# Buttons.net
KiCad netlist of a schematic drawn in Altium Designer
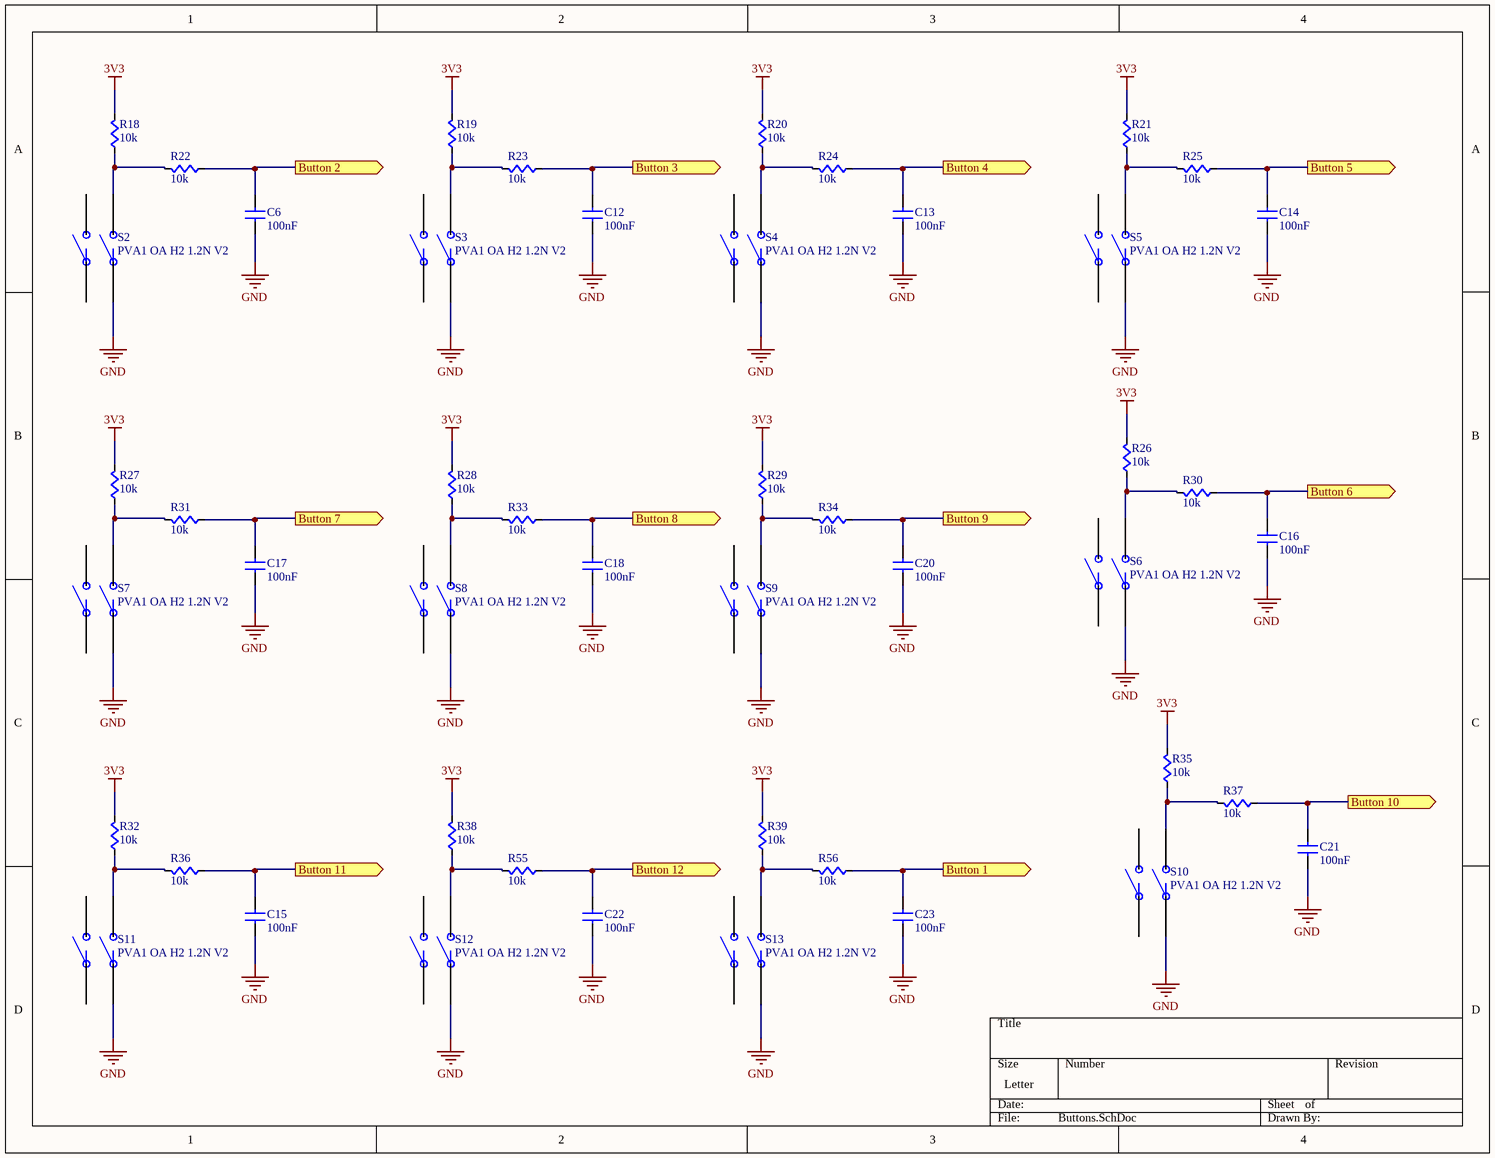
[diagram p0: Buttons.SchDoc]

(export (version "E")
  (design (tool "Eeschema 10.0.6"))
  (components
    (comp (ref "C6")
      (value "100nF")
      (footprint "CAPC0603")
      (fields (field (name "Comment") "Cap"))
      (libsource (lib "SubjuGator8") (part "Cap"))
    )
    (comp (ref "C12")
      (value "100nF")
      (footprint "CAPC0603")
      (fields (field (name "Comment") "Cap"))
      (libsource (lib "SubjuGator8") (part "Cap"))
    )
    (comp (ref "C13")
      (value "100nF")
      (footprint "CAPC0603")
      (fields (field (name "Comment") "Cap"))
      (libsource (lib "SubjuGator8") (part "Cap"))
    )
    (comp (ref "C14")
      (value "100nF")
      (footprint "CAPC0603")
      (fields (field (name "Comment") "Cap"))
      (libsource (lib "SubjuGator8") (part "Cap"))
    )
    (comp (ref "C15")
      (value "100nF")
      (footprint "CAPC0603")
      (fields (field (name "Comment") "Cap"))
      (libsource (lib "SubjuGator8") (part "Cap"))
    )
    (comp (ref "C16")
      (value "100nF")
      (footprint "CAPC0603")
      (fields (field (name "Comment") "Cap"))
      (libsource (lib "SubjuGator8") (part "Cap"))
    )
    (comp (ref "C17")
      (value "100nF")
      (footprint "CAPC0603")
      (fields (field (name "Comment") "Cap"))
      (libsource (lib "SubjuGator8") (part "Cap"))
    )
    (comp (ref "C18")
      (value "100nF")
      (footprint "CAPC0603")
      (fields (field (name "Comment") "Cap"))
      (libsource (lib "SubjuGator8") (part "Cap"))
    )
    (comp (ref "C20")
      (value "100nF")
      (footprint "CAPC0603")
      (fields (field (name "Comment") "Cap"))
      (libsource (lib "SubjuGator8") (part "Cap"))
    )
    (comp (ref "C21")
      (value "100nF")
      (footprint "CAPC0603")
      (fields (field (name "Comment") "Cap"))
      (libsource (lib "SubjuGator8") (part "Cap"))
    )
    (comp (ref "C22")
      (value "100nF")
      (footprint "CAPC0603")
      (fields (field (name "Comment") "Cap"))
      (libsource (lib "SubjuGator8") (part "Cap"))
    )
    (comp (ref "C23")
      (value "100nF")
      (footprint "CAPC0603")
      (fields (field (name "Comment") "Cap"))
      (libsource (lib "SubjuGator8") (part "Cap"))
    )
    (comp (ref "R18")
      (value "10k")
      (footprint "RES0603")
      (fields (field (name "Comment") "Res"))
      (libsource (lib "SubjuGator8") (part "Res"))
    )
    (comp (ref "R19")
      (value "10k")
      (footprint "RES0603")
      (fields (field (name "Comment") "Res"))
      (libsource (lib "SubjuGator8") (part "Res"))
    )
    (comp (ref "R20")
      (value "10k")
      (footprint "RES0603")
      (fields (field (name "Comment") "Res"))
      (libsource (lib "SubjuGator8") (part "Res"))
    )
    (comp (ref "R21")
      (value "10k")
      (footprint "RES0603")
      (fields (field (name "Comment") "Res"))
      (libsource (lib "SubjuGator8") (part "Res"))
    )
    (comp (ref "R22")
      (value "10k")
      (footprint "RES0603")
      (fields (field (name "Comment") "Res"))
      (libsource (lib "SubjuGator8") (part "Res"))
    )
    (comp (ref "R23")
      (value "10k")
      (footprint "RES0603")
      (fields (field (name "Comment") "Res"))
      (libsource (lib "SubjuGator8") (part "Res"))
    )
    (comp (ref "R24")
      (value "10k")
      (footprint "RES0603")
      (fields (field (name "Comment") "Res"))
      (libsource (lib "SubjuGator8") (part "Res"))
    )
    (comp (ref "R25")
      (value "10k")
      (footprint "RES0603")
      (fields (field (name "Comment") "Res"))
      (libsource (lib "SubjuGator8") (part "Res"))
    )
    (comp (ref "R26")
      (value "10k")
      (footprint "RES0603")
      (fields (field (name "Comment") "Res"))
      (libsource (lib "SubjuGator8") (part "Res"))
    )
    (comp (ref "R27")
      (value "10k")
      (footprint "RES0603")
      (fields (field (name "Comment") "Res"))
      (libsource (lib "SubjuGator8") (part "Res"))
    )
    (comp (ref "R28")
      (value "10k")
      (footprint "RES0603")
      (fields (field (name "Comment") "Res"))
      (libsource (lib "SubjuGator8") (part "Res"))
    )
    (comp (ref "R29")
      (value "10k")
      (footprint "RES0603")
      (fields (field (name "Comment") "Res"))
      (libsource (lib "SubjuGator8") (part "Res"))
    )
    (comp (ref "R30")
      (value "10k")
      (footprint "RES0603")
      (fields (field (name "Comment") "Res"))
      (libsource (lib "SubjuGator8") (part "Res"))
    )
    (comp (ref "R31")
      (value "10k")
      (footprint "RES0603")
      (fields (field (name "Comment") "Res"))
      (libsource (lib "SubjuGator8") (part "Res"))
    )
    (comp (ref "R32")
      (value "10k")
      (footprint "RES0603")
      (fields (field (name "Comment") "Res"))
      (libsource (lib "SubjuGator8") (part "Res"))
    )
    (comp (ref "R33")
      (value "10k")
      (footprint "RES0603")
      (fields (field (name "Comment") "Res"))
      (libsource (lib "SubjuGator8") (part "Res"))
    )
    (comp (ref "R34")
      (value "10k")
      (footprint "RES0603")
      (fields (field (name "Comment") "Res"))
      (libsource (lib "SubjuGator8") (part "Res"))
    )
    (comp (ref "R35")
      (value "10k")
      (footprint "RES0603")
      (fields (field (name "Comment") "Res"))
      (libsource (lib "SubjuGator8") (part "Res"))
    )
    (comp (ref "R36")
      (value "10k")
      (footprint "RES0603")
      (fields (field (name "Comment") "Res"))
      (libsource (lib "SubjuGator8") (part "Res"))
    )
    (comp (ref "R37")
      (value "10k")
      (footprint "RES0603")
      (fields (field (name "Comment") "Res"))
      (libsource (lib "SubjuGator8") (part "Res"))
    )
    (comp (ref "R38")
      (value "10k")
      (footprint "RES0603")
      (fields (field (name "Comment") "Res"))
      (libsource (lib "SubjuGator8") (part "Res"))
    )
    (comp (ref "R39")
      (value "10k")
      (footprint "RES0603")
      (fields (field (name "Comment") "Res"))
      (libsource (lib "SubjuGator8") (part "Res"))
    )
    (comp (ref "R55")
      (value "10k")
      (footprint "RES0603")
      (fields (field (name "Comment") "Res"))
      (libsource (lib "SubjuGator8") (part "Res"))
    )
    (comp (ref "R56")
      (value "10k")
      (footprint "RES0603")
      (fields (field (name "Comment") "Res"))
      (libsource (lib "SubjuGator8") (part "Res"))
    )
    (comp (ref "S2")
      (value "PVA1 OA H2 1.2N V2")
      (footprint "PVA1 OA H2 1.2N V2")
      (description "Pushbutton Switch DPST-NO Keyswitch Through Hole")
      (fields (field (name "MANUFACTURER") "C&K"))
      (libsource (lib "SubjuGator8") (part "PVA1 OA H2 1.2N V2"))
    )
    (comp (ref "S3")
      (value "PVA1 OA H2 1.2N V2")
      (footprint "PVA1 OA H2 1.2N V2")
      (description "Pushbutton Switch DPST-NO Keyswitch Through Hole")
      (fields (field (name "MANUFACTURER") "C&K"))
      (libsource (lib "SubjuGator8") (part "PVA1 OA H2 1.2N V2"))
    )
    (comp (ref "S4")
      (value "PVA1 OA H2 1.2N V2")
      (footprint "PVA1 OA H2 1.2N V2")
      (description "Pushbutton Switch DPST-NO Keyswitch Through Hole")
      (fields (field (name "MANUFACTURER") "C&K"))
      (libsource (lib "SubjuGator8") (part "PVA1 OA H2 1.2N V2"))
    )
    (comp (ref "S5")
      (value "PVA1 OA H2 1.2N V2")
      (footprint "PVA1 OA H2 1.2N V2")
      (description "Pushbutton Switch DPST-NO Keyswitch Through Hole")
      (fields (field (name "MANUFACTURER") "C&K"))
      (libsource (lib "SubjuGator8") (part "PVA1 OA H2 1.2N V2"))
    )
    (comp (ref "S6")
      (value "PVA1 OA H2 1.2N V2")
      (footprint "PVA1 OA H2 1.2N V2")
      (description "Pushbutton Switch DPST-NO Keyswitch Through Hole")
      (fields (field (name "MANUFACTURER") "C&K"))
      (libsource (lib "SubjuGator8") (part "PVA1 OA H2 1.2N V2"))
    )
    (comp (ref "S7")
      (value "PVA1 OA H2 1.2N V2")
      (footprint "PVA1 OA H2 1.2N V2")
      (description "Pushbutton Switch DPST-NO Keyswitch Through Hole")
      (fields (field (name "MANUFACTURER") "C&K"))
      (libsource (lib "SubjuGator8") (part "PVA1 OA H2 1.2N V2"))
    )
    (comp (ref "S8")
      (value "PVA1 OA H2 1.2N V2")
      (footprint "PVA1 OA H2 1.2N V2")
      (description "Pushbutton Switch DPST-NO Keyswitch Through Hole")
      (fields (field (name "MANUFACTURER") "C&K"))
      (libsource (lib "SubjuGator8") (part "PVA1 OA H2 1.2N V2"))
    )
    (comp (ref "S9")
      (value "PVA1 OA H2 1.2N V2")
      (footprint "PVA1 OA H2 1.2N V2")
      (description "Pushbutton Switch DPST-NO Keyswitch Through Hole")
      (fields (field (name "MANUFACTURER") "C&K"))
      (libsource (lib "SubjuGator8") (part "PVA1 OA H2 1.2N V2"))
    )
    (comp (ref "S10")
      (value "PVA1 OA H2 1.2N V2")
      (footprint "PVA1 OA H2 1.2N V2")
      (description "Pushbutton Switch DPST-NO Keyswitch Through Hole")
      (fields (field (name "MANUFACTURER") "C&K"))
      (libsource (lib "SubjuGator8") (part "PVA1 OA H2 1.2N V2"))
    )
    (comp (ref "S11")
      (value "PVA1 OA H2 1.2N V2")
      (footprint "PVA1 OA H2 1.2N V2")
      (description "Pushbutton Switch DPST-NO Keyswitch Through Hole")
      (fields (field (name "MANUFACTURER") "C&K"))
      (libsource (lib "SubjuGator8") (part "PVA1 OA H2 1.2N V2"))
    )
    (comp (ref "S12")
      (value "PVA1 OA H2 1.2N V2")
      (footprint "PVA1 OA H2 1.2N V2")
      (description "Pushbutton Switch DPST-NO Keyswitch Through Hole")
      (fields (field (name "MANUFACTURER") "C&K"))
      (libsource (lib "SubjuGator8") (part "PVA1 OA H2 1.2N V2"))
    )
    (comp (ref "S13")
      (value "PVA1 OA H2 1.2N V2")
      (footprint "PVA1 OA H2 1.2N V2")
      (description "Pushbutton Switch DPST-NO Keyswitch Through Hole")
      (fields (field (name "MANUFACTURER") "C&K"))
      (libsource (lib "SubjuGator8") (part "PVA1 OA H2 1.2N V2"))
    )
  )
  (nets
    (net (code "1") (name "/Button 1") (class "Default")
      (node (ref "C23") (pin "1") (pinfunction "A_1") (pintype "passive"))
      (node (ref "R56") (pin "2") (pinfunction "B_2") (pintype "passive"))
    )
    (net (code "2") (name "/Button 2") (class "Default")
      (node (ref "C6") (pin "1") (pinfunction "A_1") (pintype "passive"))
      (node (ref "R22") (pin "2") (pinfunction "B_2") (pintype "passive"))
    )
    (net (code "3") (name "/Button 3") (class "Default")
      (node (ref "C12") (pin "1") (pinfunction "A_1") (pintype "passive"))
      (node (ref "R23") (pin "2") (pinfunction "B_2") (pintype "passive"))
    )
    (net (code "4") (name "/Button 4") (class "Default")
      (node (ref "C13") (pin "1") (pinfunction "A_1") (pintype "passive"))
      (node (ref "R24") (pin "2") (pinfunction "B_2") (pintype "passive"))
    )
    (net (code "5") (name "/Button 5") (class "Default")
      (node (ref "C14") (pin "1") (pinfunction "A_1") (pintype "passive"))
      (node (ref "R25") (pin "2") (pinfunction "B_2") (pintype "passive"))
    )
    (net (code "6") (name "/Button 6") (class "Default")
      (node (ref "C16") (pin "1") (pinfunction "A_1") (pintype "passive"))
      (node (ref "R30") (pin "2") (pinfunction "B_2") (pintype "passive"))
    )
    (net (code "7") (name "/Button 7") (class "Default")
      (node (ref "C17") (pin "1") (pinfunction "A_1") (pintype "passive"))
      (node (ref "R31") (pin "2") (pinfunction "B_2") (pintype "passive"))
    )
    (net (code "8") (name "/Button 8") (class "Default")
      (node (ref "C18") (pin "1") (pinfunction "A_1") (pintype "passive"))
      (node (ref "R33") (pin "2") (pinfunction "B_2") (pintype "passive"))
    )
    (net (code "9") (name "/Button 9") (class "Default")
      (node (ref "C20") (pin "1") (pinfunction "A_1") (pintype "passive"))
      (node (ref "R34") (pin "2") (pinfunction "B_2") (pintype "passive"))
    )
    (net (code "10") (name "/Button 10") (class "Default")
      (node (ref "C21") (pin "1") (pinfunction "A_1") (pintype "passive"))
      (node (ref "R37") (pin "2") (pinfunction "B_2") (pintype "passive"))
    )
    (net (code "11") (name "/Button 11") (class "Default")
      (node (ref "C15") (pin "1") (pinfunction "A_1") (pintype "passive"))
      (node (ref "R36") (pin "2") (pinfunction "B_2") (pintype "passive"))
    )
    (net (code "12") (name "/Button 12") (class "Default")
      (node (ref "C22") (pin "1") (pinfunction "A_1") (pintype "passive"))
      (node (ref "R55") (pin "2") (pinfunction "B_2") (pintype "passive"))
    )
    (net (code "13") (name "3V3") (class "Default")
      (node (ref "R18") (pin "1") (pinfunction "A_1") (pintype "passive"))
      (node (ref "R19") (pin "1") (pinfunction "A_1") (pintype "passive"))
      (node (ref "R20") (pin "1") (pinfunction "A_1") (pintype "passive"))
      (node (ref "R21") (pin "1") (pinfunction "A_1") (pintype "passive"))
      (node (ref "R26") (pin "1") (pinfunction "A_1") (pintype "passive"))
      (node (ref "R27") (pin "1") (pinfunction "A_1") (pintype "passive"))
      (node (ref "R28") (pin "1") (pinfunction "A_1") (pintype "passive"))
      (node (ref "R29") (pin "1") (pinfunction "A_1") (pintype "passive"))
      (node (ref "R32") (pin "1") (pinfunction "A_1") (pintype "passive"))
      (node (ref "R35") (pin "1") (pinfunction "A_1") (pintype "passive"))
      (node (ref "R38") (pin "1") (pinfunction "A_1") (pintype "passive"))
      (node (ref "R39") (pin "1") (pinfunction "A_1") (pintype "passive"))
    )
    (net (code "14") (name "GND") (class "Default")
      (node (ref "C12") (pin "2") (pinfunction "B_2") (pintype "passive"))
      (node (ref "C13") (pin "2") (pinfunction "B_2") (pintype "passive"))
      (node (ref "C14") (pin "2") (pinfunction "B_2") (pintype "passive"))
      (node (ref "C15") (pin "2") (pinfunction "B_2") (pintype "passive"))
      (node (ref "C16") (pin "2") (pinfunction "B_2") (pintype "passive"))
      (node (ref "C17") (pin "2") (pinfunction "B_2") (pintype "passive"))
      (node (ref "C18") (pin "2") (pinfunction "B_2") (pintype "passive"))
      (node (ref "C20") (pin "2") (pinfunction "B_2") (pintype "passive"))
      (node (ref "C21") (pin "2") (pinfunction "B_2") (pintype "passive"))
      (node (ref "C22") (pin "2") (pinfunction "B_2") (pintype "passive"))
      (node (ref "C23") (pin "2") (pinfunction "B_2") (pintype "passive"))
      (node (ref "C6") (pin "2") (pinfunction "B_2") (pintype "passive"))
      (node (ref "S10") (pin "3") (pinfunction "3_3") (pintype "passive"))
      (node (ref "S11") (pin "3") (pinfunction "3_3") (pintype "passive"))
      (node (ref "S12") (pin "3") (pinfunction "3_3") (pintype "passive"))
      (node (ref "S13") (pin "3") (pinfunction "3_3") (pintype "passive"))
      (node (ref "S2") (pin "3") (pinfunction "3_3") (pintype "passive"))
      (node (ref "S3") (pin "3") (pinfunction "3_3") (pintype "passive"))
      (node (ref "S4") (pin "3") (pinfunction "3_3") (pintype "passive"))
      (node (ref "S5") (pin "3") (pinfunction "3_3") (pintype "passive"))
      (node (ref "S6") (pin "3") (pinfunction "3_3") (pintype "passive"))
      (node (ref "S7") (pin "3") (pinfunction "3_3") (pintype "passive"))
      (node (ref "S8") (pin "3") (pinfunction "3_3") (pintype "passive"))
      (node (ref "S9") (pin "3") (pinfunction "3_3") (pintype "passive"))
    )
    (net (code "15") (name "Net-(R18-B)") (class "Default")
      (node (ref "R18") (pin "2") (pinfunction "B_2") (pintype "passive"))
      (node (ref "R22") (pin "1") (pinfunction "A_1") (pintype "passive"))
      (node (ref "S2") (pin "4") (pinfunction "4_4") (pintype "passive"))
    )
    (net (code "16") (name "Net-(R19-B)") (class "Default")
      (node (ref "R19") (pin "2") (pinfunction "B_2") (pintype "passive"))
      (node (ref "R23") (pin "1") (pinfunction "A_1") (pintype "passive"))
      (node (ref "S3") (pin "4") (pinfunction "4_4") (pintype "passive"))
    )
    (net (code "17") (name "Net-(R20-B)") (class "Default")
      (node (ref "R20") (pin "2") (pinfunction "B_2") (pintype "passive"))
      (node (ref "R24") (pin "1") (pinfunction "A_1") (pintype "passive"))
      (node (ref "S4") (pin "4") (pinfunction "4_4") (pintype "passive"))
    )
    (net (code "18") (name "Net-(R21-B)") (class "Default")
      (node (ref "R21") (pin "2") (pinfunction "B_2") (pintype "passive"))
      (node (ref "R25") (pin "1") (pinfunction "A_1") (pintype "passive"))
      (node (ref "S5") (pin "4") (pinfunction "4_4") (pintype "passive"))
    )
    (net (code "19") (name "Net-(R26-B)") (class "Default")
      (node (ref "R26") (pin "2") (pinfunction "B_2") (pintype "passive"))
      (node (ref "R30") (pin "1") (pinfunction "A_1") (pintype "passive"))
      (node (ref "S6") (pin "4") (pinfunction "4_4") (pintype "passive"))
    )
    (net (code "20") (name "Net-(R27-B)") (class "Default")
      (node (ref "R27") (pin "2") (pinfunction "B_2") (pintype "passive"))
      (node (ref "R31") (pin "1") (pinfunction "A_1") (pintype "passive"))
      (node (ref "S7") (pin "4") (pinfunction "4_4") (pintype "passive"))
    )
    (net (code "21") (name "Net-(R28-B)") (class "Default")
      (node (ref "R28") (pin "2") (pinfunction "B_2") (pintype "passive"))
      (node (ref "R33") (pin "1") (pinfunction "A_1") (pintype "passive"))
      (node (ref "S8") (pin "4") (pinfunction "4_4") (pintype "passive"))
    )
    (net (code "22") (name "Net-(R29-B)") (class "Default")
      (node (ref "R29") (pin "2") (pinfunction "B_2") (pintype "passive"))
      (node (ref "R34") (pin "1") (pinfunction "A_1") (pintype "passive"))
      (node (ref "S9") (pin "4") (pinfunction "4_4") (pintype "passive"))
    )
    (net (code "23") (name "Net-(R32-B)") (class "Default")
      (node (ref "R32") (pin "2") (pinfunction "B_2") (pintype "passive"))
      (node (ref "R36") (pin "1") (pinfunction "A_1") (pintype "passive"))
      (node (ref "S11") (pin "4") (pinfunction "4_4") (pintype "passive"))
    )
    (net (code "24") (name "Net-(R35-B)") (class "Default")
      (node (ref "R35") (pin "2") (pinfunction "B_2") (pintype "passive"))
      (node (ref "R37") (pin "1") (pinfunction "A_1") (pintype "passive"))
      (node (ref "S10") (pin "4") (pinfunction "4_4") (pintype "passive"))
    )
    (net (code "25") (name "Net-(R38-B)") (class "Default")
      (node (ref "R38") (pin "2") (pinfunction "B_2") (pintype "passive"))
      (node (ref "R55") (pin "1") (pinfunction "A_1") (pintype "passive"))
      (node (ref "S12") (pin "4") (pinfunction "4_4") (pintype "passive"))
    )
    (net (code "26") (name "Net-(R39-B)") (class "Default")
      (node (ref "R39") (pin "2") (pinfunction "B_2") (pintype "passive"))
      (node (ref "R56") (pin "1") (pinfunction "A_1") (pintype "passive"))
      (node (ref "S13") (pin "4") (pinfunction "4_4") (pintype "passive"))
    )
    (net (code "27") (name "unconnected-(S2-Pad1)") (class "Default")
      (node (ref "S2") (pin "1") (pinfunction "1_1") (pintype "passive"))
    )
    (net (code "28") (name "unconnected-(S2-Pad2)") (class "Default")
      (node (ref "S2") (pin "2") (pinfunction "2_2") (pintype "passive"))
    )
    (net (code "29") (name "unconnected-(S3-Pad1)") (class "Default")
      (node (ref "S3") (pin "1") (pinfunction "1_1") (pintype "passive"))
    )
    (net (code "30") (name "unconnected-(S3-Pad2)") (class "Default")
      (node (ref "S3") (pin "2") (pinfunction "2_2") (pintype "passive"))
    )
    (net (code "31") (name "unconnected-(S4-Pad1)") (class "Default")
      (node (ref "S4") (pin "1") (pinfunction "1_1") (pintype "passive"))
    )
    (net (code "32") (name "unconnected-(S4-Pad2)") (class "Default")
      (node (ref "S4") (pin "2") (pinfunction "2_2") (pintype "passive"))
    )
    (net (code "33") (name "unconnected-(S5-Pad1)") (class "Default")
      (node (ref "S5") (pin "1") (pinfunction "1_1") (pintype "passive"))
    )
    (net (code "34") (name "unconnected-(S5-Pad2)") (class "Default")
      (node (ref "S5") (pin "2") (pinfunction "2_2") (pintype "passive"))
    )
    (net (code "35") (name "unconnected-(S6-Pad1)") (class "Default")
      (node (ref "S6") (pin "1") (pinfunction "1_1") (pintype "passive"))
    )
    (net (code "36") (name "unconnected-(S6-Pad2)") (class "Default")
      (node (ref "S6") (pin "2") (pinfunction "2_2") (pintype "passive"))
    )
    (net (code "37") (name "unconnected-(S7-Pad1)") (class "Default")
      (node (ref "S7") (pin "1") (pinfunction "1_1") (pintype "passive"))
    )
    (net (code "38") (name "unconnected-(S7-Pad2)") (class "Default")
      (node (ref "S7") (pin "2") (pinfunction "2_2") (pintype "passive"))
    )
    (net (code "39") (name "unconnected-(S8-Pad1)") (class "Default")
      (node (ref "S8") (pin "1") (pinfunction "1_1") (pintype "passive"))
    )
    (net (code "40") (name "unconnected-(S8-Pad2)") (class "Default")
      (node (ref "S8") (pin "2") (pinfunction "2_2") (pintype "passive"))
    )
    (net (code "41") (name "unconnected-(S9-Pad1)") (class "Default")
      (node (ref "S9") (pin "1") (pinfunction "1_1") (pintype "passive"))
    )
    (net (code "42") (name "unconnected-(S9-Pad2)") (class "Default")
      (node (ref "S9") (pin "2") (pinfunction "2_2") (pintype "passive"))
    )
    (net (code "43") (name "unconnected-(S10-Pad1)") (class "Default")
      (node (ref "S10") (pin "1") (pinfunction "1_1") (pintype "passive"))
    )
    (net (code "44") (name "unconnected-(S10-Pad2)") (class "Default")
      (node (ref "S10") (pin "2") (pinfunction "2_2") (pintype "passive"))
    )
    (net (code "45") (name "unconnected-(S11-Pad1)") (class "Default")
      (node (ref "S11") (pin "1") (pinfunction "1_1") (pintype "passive"))
    )
    (net (code "46") (name "unconnected-(S11-Pad2)") (class "Default")
      (node (ref "S11") (pin "2") (pinfunction "2_2") (pintype "passive"))
    )
    (net (code "47") (name "unconnected-(S12-Pad1)") (class "Default")
      (node (ref "S12") (pin "1") (pinfunction "1_1") (pintype "passive"))
    )
    (net (code "48") (name "unconnected-(S12-Pad2)") (class "Default")
      (node (ref "S12") (pin "2") (pinfunction "2_2") (pintype "passive"))
    )
    (net (code "49") (name "unconnected-(S13-Pad1)") (class "Default")
      (node (ref "S13") (pin "1") (pinfunction "1_1") (pintype "passive"))
    )
    (net (code "50") (name "unconnected-(S13-Pad2)") (class "Default")
      (node (ref "S13") (pin "2") (pinfunction "2_2") (pintype "passive"))
    )
  )
)
